# powerboard.net
KiCad netlist of a schematic drawn in EAGLE
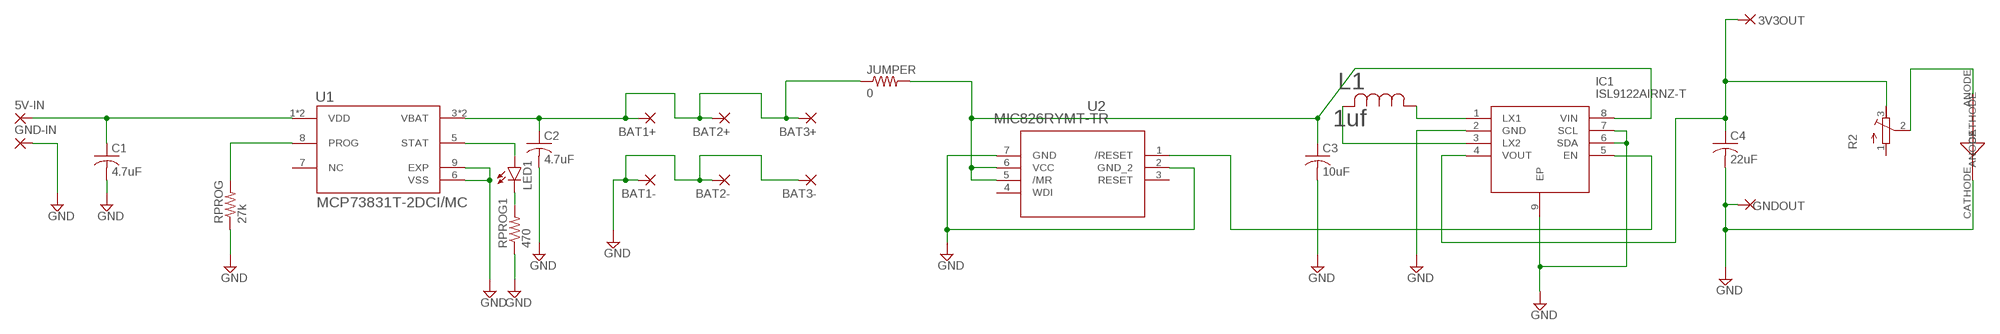
[diagram p0: schematic, sheet 1]

(export (version "E")
  (design (tool "Eeschema 10.0.6"))
  (components
    (comp (ref "3V3OUT")
      (value "2,54/0,9")
      (footprint "eagle-import:2,54_0,9")
      (libsource (lib "eagle-import") (part "2,54/0,9"))
    )
    (comp (ref "5V-IN")
      (value "2,54/0,9")
      (footprint "eagle-import:2,54_0,9")
      (libsource (lib "eagle-import") (part "2,54/0,9"))
    )
    (comp (ref "BAT1+")
      (value "2,54/0,9")
      (footprint "eagle-import:2,54_0,9")
      (libsource (lib "eagle-import") (part "2,54/0,9"))
    )
    (comp (ref "BAT1-")
      (value "2,54/0,9")
      (footprint "eagle-import:2,54_0,9")
      (libsource (lib "eagle-import") (part "2,54/0,9"))
    )
    (comp (ref "BAT2+")
      (value "2,54/0,9")
      (footprint "eagle-import:2,54_0,9")
      (libsource (lib "eagle-import") (part "2,54/0,9"))
    )
    (comp (ref "BAT2-")
      (value "2,54/0,9")
      (footprint "eagle-import:2,54_0,9")
      (libsource (lib "eagle-import") (part "2,54/0,9"))
    )
    (comp (ref "BAT3+")
      (value "2,54/0,9")
      (footprint "eagle-import:2,54_0,9")
      (libsource (lib "eagle-import") (part "2,54/0,9"))
    )
    (comp (ref "BAT3-")
      (value "2,54/0,9")
      (footprint "eagle-import:2,54_0,9")
      (libsource (lib "eagle-import") (part "2,54/0,9"))
    )
    (comp (ref "C1")
      (value "4.7uF")
      (footprint "eagle-import:C0603K")
      (libsource (lib "eagle-import") (part "C-USC0603K"))
    )
    (comp (ref "C2")
      (value "4.7uF")
      (footprint "eagle-import:C0603K")
      (libsource (lib "eagle-import") (part "C-USC0603K"))
    )
    (comp (ref "C3")
      (value "10uF")
      (footprint "eagle-import:C0603K")
      (libsource (lib "eagle-import") (part "C-USC0603K"))
    )
    (comp (ref "C4")
      (value "22uF")
      (footprint "eagle-import:C0603K")
      (libsource (lib "eagle-import") (part "C-USC0603K"))
    )
    (comp (ref "GND-IN")
      (value "2,54/0,9")
      (footprint "eagle-import:2,54_0,9")
      (libsource (lib "eagle-import") (part "2,54/0,9"))
    )
    (comp (ref "GNDOUT")
      (value "2,54/0,9")
      (footprint "eagle-import:2,54_0,9")
      (libsource (lib "eagle-import") (part "2,54/0,9"))
    )
    (comp (ref "IC1")
      (value "ISL9122AIRNZ-T")
      (footprint "eagle-import:SON50P300X200X100-9N")
      (fields (field (name "MOUSER_PART_NUMBER") "968-ISL9122AIRNZ-T"))
      (libsource (lib "eagle-import") (part "ISL9122AIRNZ-T"))
    )
    (comp (ref "JUMPER")
      (value "0")
      (footprint "eagle-import:R0805")
      (libsource (lib "eagle-import") (part "R-US_R0805"))
    )
    (comp (ref "L1")
      (value "1uf")
      (footprint "eagle-import:IND_IHHP-0806ZH-01_VIS")
      (fields
        (field (name "MANUFACTURER_PART_NUMBER") "IHHP0806ZHER1R0M01")
        (field (name "COPYRIGHT") "Copyright (C) 2023 Ultra Librarian. All rights reserved.")
      )
      (libsource (lib "eagle-import") (part "IHHP0806ZHER1R0M01"))
    )
    (comp (ref "LED1")
      (value "LEDCHIPLED_0603")
      (footprint "eagle-import:CHIPLED_0603")
      (libsource (lib "eagle-import") (part "LEDCHIPLED_0603"))
    )
    (comp (ref "R2")
      (value "R-TRIMM3165W")
      (footprint "eagle-import:RTRIM3165W")
      (libsource (lib "eagle-import") (part "R-TRIMM3165W"))
    )
    (comp (ref "RPROG")
      (value "27k")
      (footprint "eagle-import:R0402")
      (libsource (lib "eagle-import") (part "R-US_R0402"))
    )
    (comp (ref "RPROG1")
      (value "470")
      (footprint "eagle-import:R0402")
      (libsource (lib "eagle-import") (part "R-US_R0402"))
    )
    (comp (ref "U$1")
      (value "CHIPLED")
      (footprint "eagle-import:CHIPLED2828")
      (libsource (lib "eagle-import") (part "CHIPLED"))
    )
    (comp (ref "U1")
      (value "MCP73831T-2DCI/MC")
      (footprint "eagle-import:SON50P200X300X100-9N")
      (fields (field (name "MF") "Microchip"))
      (libsource (lib "eagle-import") (part "MCP73831T-2DCI/MC"))
    )
    (comp (ref "U2")
      (value "MIC826RYMT-TR")
      (footprint "eagle-import:UDFN6_HKA_MCH")
      (fields (field (name "COPYRIGHT") "Copyright (C) 2023 Ultra Librarian. All rights reserved."))
      (libsource (lib "eagle-import") (part "MIC826RYMT-TR"))
    )
  )
  (nets
    (net (code "1") (name "GND") (class "Default")
      (node (ref "BAT1-") (pin "1") (pinfunction "P_1") (pintype "passive"))
      (node (ref "BAT2-") (pin "1") (pinfunction "P_1") (pintype "passive"))
      (node (ref "BAT3-") (pin "1") (pinfunction "P_1") (pintype "passive"))
      (node (ref "C1") (pin "2") (pinfunction "2_2") (pintype "passive"))
      (node (ref "C2") (pin "2") (pinfunction "2_2") (pintype "passive"))
      (node (ref "C3") (pin "2") (pinfunction "2_2") (pintype "passive"))
      (node (ref "C4") (pin "2") (pinfunction "2_2") (pintype "passive"))
      (node (ref "GND-IN") (pin "1") (pinfunction "P_1") (pintype "passive"))
      (node (ref "GNDOUT") (pin "1") (pinfunction "P_1") (pintype "passive"))
      (node (ref "IC1") (pin "2") (pinfunction "GND_2") (pintype "bidirectional"))
      (node (ref "IC1") (pin "6") (pinfunction "SDA_6") (pintype "bidirectional"))
      (node (ref "IC1") (pin "7") (pinfunction "SCL_7") (pintype "bidirectional"))
      (node (ref "IC1") (pin "9") (pinfunction "EP_9") (pintype "bidirectional"))
      (node (ref "RPROG") (pin "1") (pinfunction "1_1") (pintype "passive"))
      (node (ref "RPROG1") (pin "1") (pinfunction "1_1") (pintype "passive"))
      (node (ref "U$1") (pin "CATHODE") (pinfunction "CATHODE_CATHODE") (pintype "bidirectional"))
      (node (ref "U1") (pin "6") (pinfunction "VSS_6") (pintype "power_in"))
      (node (ref "U1") (pin "9") (pinfunction "EXP_9") (pintype "power_in"))
      (node (ref "U2") (pin "2") (pinfunction "GND_2_2") (pintype "power_in"))
      (node (ref "U2") (pin "7") (pinfunction "GND_7") (pintype "passive"))
    )
    (net (code "2") (name "Net-(3V3OUT-P)") (class "Default")
      (node (ref "3V3OUT") (pin "1") (pinfunction "P_1") (pintype "passive"))
      (node (ref "C4") (pin "1") (pinfunction "1_1") (pintype "passive"))
      (node (ref "IC1") (pin "4") (pinfunction "VOUT_4") (pintype "bidirectional"))
      (node (ref "R2") (pin "3") (pinfunction "E_3") (pintype "passive"))
    )
    (net (code "3") (name "Net-(5V-IN-P)") (class "Default")
      (node (ref "5V-IN") (pin "1") (pinfunction "P_1") (pintype "passive"))
      (node (ref "C1") (pin "1") (pinfunction "1_1") (pintype "passive"))
      (node (ref "U1") (pin "1") (pinfunction "VDD_1") (pintype "input"))
      (node (ref "U1") (pin "2") (pinfunction "VDD_2") (pintype "input"))
    )
    (net (code "4") (name "Net-(BAT1+-P)") (class "Default")
      (node (ref "BAT1+") (pin "1") (pinfunction "P_1") (pintype "passive"))
      (node (ref "BAT2+") (pin "1") (pinfunction "P_1") (pintype "passive"))
      (node (ref "BAT3+") (pin "1") (pinfunction "P_1") (pintype "passive"))
      (node (ref "C2") (pin "1") (pinfunction "1_1") (pintype "passive"))
      (node (ref "JUMPER") (pin "1") (pinfunction "1_1") (pintype "passive"))
      (node (ref "U1") (pin "3") (pinfunction "VBAT_3") (pintype "output"))
      (node (ref "U1") (pin "4") (pinfunction "VBAT_4") (pintype "output"))
    )
    (net (code "5") (name "Net-(IC1-EN)") (class "Default")
      (node (ref "IC1") (pin "5") (pinfunction "EN_5") (pintype "bidirectional"))
      (node (ref "U2") (pin "1") (pinfunction "/RESET_1") (pintype "output"))
    )
    (net (code "6") (name "Net-(IC1-LX1)") (class "Default")
      (node (ref "IC1") (pin "1") (pinfunction "LX1_1") (pintype "bidirectional"))
      (node (ref "L1") (pin "1") (pinfunction "1_1") (pintype "passive"))
    )
    (net (code "7") (name "Net-(IC1-LX2)") (class "Default")
      (node (ref "IC1") (pin "3") (pinfunction "LX2_3") (pintype "bidirectional"))
      (node (ref "L1") (pin "2") (pinfunction "2_2") (pintype "passive"))
    )
    (net (code "8") (name "Net-(IC1-VIN)") (class "Default")
      (node (ref "C3") (pin "1") (pinfunction "1_1") (pintype "passive"))
      (node (ref "IC1") (pin "8") (pinfunction "VIN_8") (pintype "bidirectional"))
      (node (ref "JUMPER") (pin "2") (pinfunction "2_2") (pintype "passive"))
      (node (ref "U2") (pin "5") (pinfunction "/MR_5") (pintype "input"))
      (node (ref "U2") (pin "6") (pinfunction "VCC_6") (pintype "power_in"))
    )
    (net (code "9") (name "Net-(LED1-PadC)") (class "Default")
      (node (ref "LED1") (pin "C") (pinfunction "C_C") (pintype "passive"))
      (node (ref "RPROG1") (pin "2") (pinfunction "2_2") (pintype "passive"))
    )
    (net (code "10") (name "Net-(R2-S)") (class "Default")
      (node (ref "R2") (pin "2") (pinfunction "S_2") (pintype "passive"))
      (node (ref "U$1") (pin "ANODE") (pinfunction "ANODE_ANODE") (pintype "bidirectional"))
    )
    (net (code "11") (name "Net-(U1-PROG)") (class "Default")
      (node (ref "RPROG") (pin "2") (pinfunction "2_2") (pintype "passive"))
      (node (ref "U1") (pin "8") (pinfunction "PROG_8") (pintype "input"))
    )
    (net (code "12") (name "Net-(U1-STAT)") (class "Default")
      (node (ref "LED1") (pin "A") (pinfunction "A_A") (pintype "passive"))
      (node (ref "U1") (pin "5") (pinfunction "STAT_5") (pintype "output"))
    )
    (net (code "13") (name "unconnected-(R2-A-Pad1)") (class "Default")
      (node (ref "R2") (pin "1") (pinfunction "A_1") (pintype "passive"))
    )
    (net (code "14") (name "unconnected-(U1-NC-Pad7)") (class "Default")
      (node (ref "U1") (pin "7") (pinfunction "NC_7") (pintype "no_connect"))
    )
    (net (code "15") (name "unconnected-(U2-RESET-Pad3)") (class "Default")
      (node (ref "U2") (pin "3") (pinfunction "RESET_3") (pintype "output"))
    )
    (net (code "16") (name "unconnected-(U2-WDI-Pad4)") (class "Default")
      (node (ref "U2") (pin "4") (pinfunction "WDI_4") (pintype "input"))
    )
  )
)
